# bulb-2.net
KiCad netlist of a schematic drawn in EAGLE
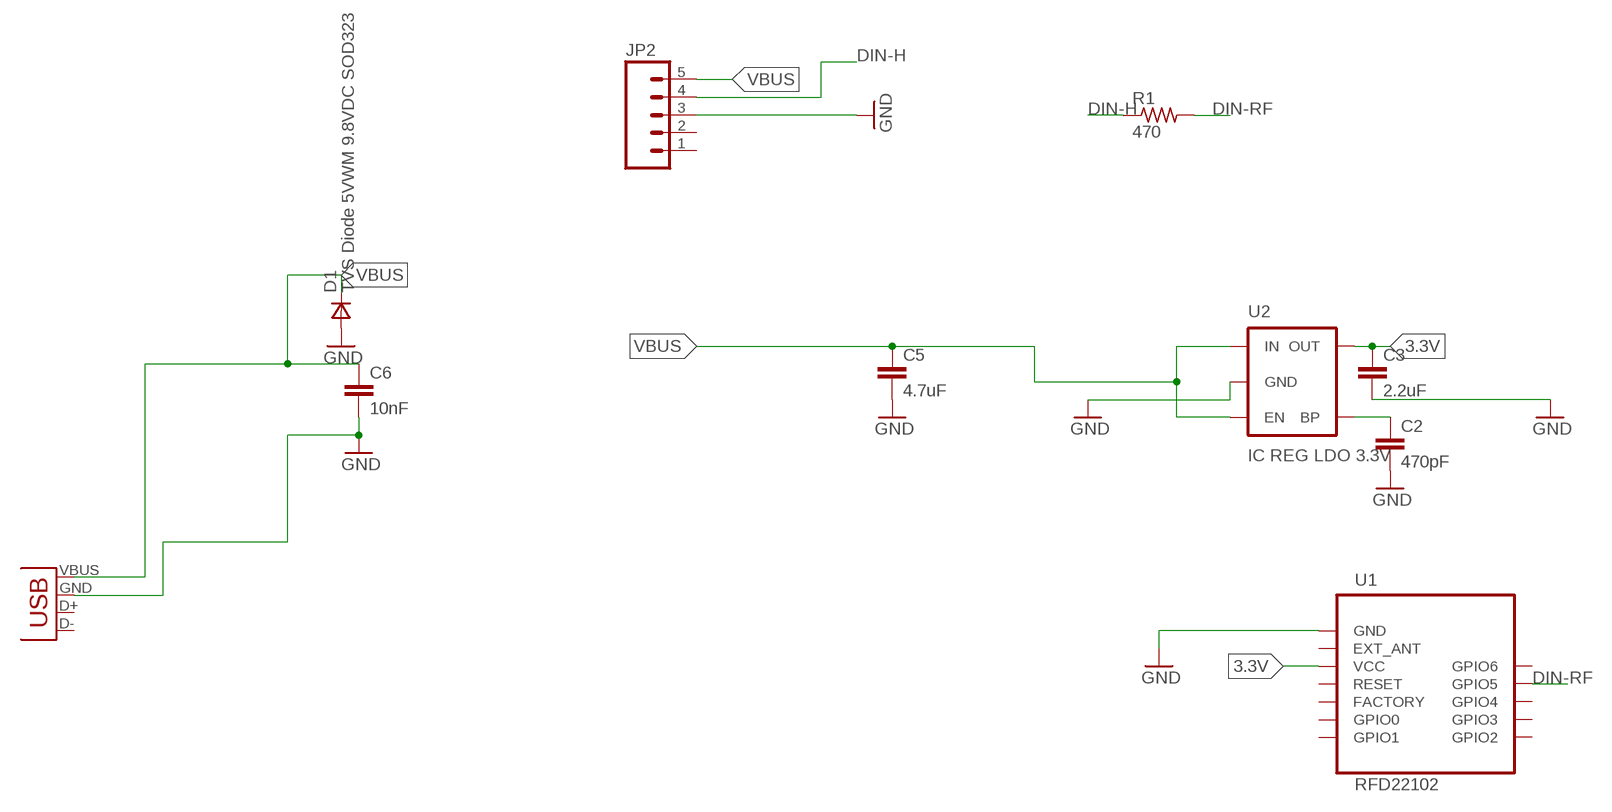
[diagram p0: schematic, sheet 1]

(export (version "E")
  (design (tool "Eeschema 10.0.6"))
  (components
    (comp (ref "C2")
      (value "470pF")
      (footprint "eagle-import:0603-CAP")
      (libsource (lib "eagle-import") (part "470PF-50V-5%(0603)SMD"))
    )
    (comp (ref "C3")
      (value "2.2uF")
      (footprint "eagle-import:0603-CAP")
      (libsource (lib "eagle-import") (part "2.2UF-10V-20%(0603)"))
    )
    (comp (ref "C5")
      (value "4.7uF")
      (footprint "eagle-import:0603-CAP")
      (libsource (lib "eagle-import") (part "4.7UF-6.3V-10%(0603)0603"))
    )
    (comp (ref "C6")
      (value "10nF")
      (footprint "eagle-import:0603-CAP")
      (libsource (lib "eagle-import") (part "10NF/10000PF-50V-10%(0603)"))
    )
    (comp (ref "D1")
      (value "TVS Diode 5VWM 9.8VDC SOD323")
      (footprint "eagle-import:SOD323")
      (fields (field (name "MPN") "CDSOD323-T05C"))
      (libsource (lib "eagle-import") (part "DSOD323"))
    )
    (comp (ref "JP1")
      (value "USB-A-H")
      (footprint "eagle-import:USB-A-H")
      (libsource (lib "eagle-import") (part "USB-A-H"))
    )
    (comp (ref "JP2")
      (value "M05PTH")
      (footprint "eagle-import:1X05")
      (libsource (lib "eagle-import") (part "M05PTH"))
    )
    (comp (ref "R1")
      (value "470")
      (footprint "eagle-import:R0603")
      (libsource (lib "eagle-import") (part "R-US_R0603"))
    )
    (comp (ref "U1")
      (value "RFD22102")
      (footprint "eagle-import:RFD22102")
      (libsource (lib "eagle-import") (part "RFD22102"))
    )
    (comp (ref "U2")
      (value "IC REG LDO 3.3V")
      (footprint "eagle-import:SOT23-5")
      (libsource (lib "eagle-import") (part "MIC52053.3V"))
    )
  )
  (nets
    (net (code "1") (name "/DIN-H") (class "Default")
      (node (ref "JP2") (pin "4") (pinfunction "4_4") (pintype "passive"))
      (node (ref "R1") (pin "1") (pinfunction "1_1") (pintype "passive"))
    )
    (net (code "2") (name "/DIN-RF") (class "Default")
      (node (ref "R1") (pin "2") (pinfunction "2_2") (pintype "passive"))
      (node (ref "U1") (pin "GPIO5") (pinfunction "GPIO5_GPIO5") (pintype "bidirectional"))
    )
    (net (code "3") (name "3.3V") (class "Default")
      (node (ref "C3") (pin "1") (pinfunction "1_1") (pintype "passive"))
      (node (ref "U1") (pin "VCC") (pinfunction "VCC_VCC") (pintype "power_in"))
      (node (ref "U2") (pin "5") (pinfunction "OUT_5") (pintype "passive"))
    )
    (net (code "4") (name "GND") (class "Default")
      (node (ref "C2") (pin "2") (pinfunction "2_2") (pintype "passive"))
      (node (ref "C3") (pin "2") (pinfunction "2_2") (pintype "passive"))
      (node (ref "C5") (pin "2") (pinfunction "2_2") (pintype "passive"))
      (node (ref "C6") (pin "2") (pinfunction "2_2") (pintype "passive"))
      (node (ref "D1") (pin "2") (pinfunction "A_2") (pintype "passive"))
      (node (ref "JP1") (pin "GND") (pinfunction "VBUS_GND") (pintype "bidirectional"))
      (node (ref "JP2") (pin "3") (pinfunction "3_3") (pintype "passive"))
      (node (ref "U1") (pin "GND") (pinfunction "GND_GND") (pintype "power_in"))
      (node (ref "U2") (pin "2") (pinfunction "GND_2") (pintype "input"))
    )
    (net (code "5") (name "Net-(U2-BP)") (class "Default")
      (node (ref "C2") (pin "1") (pinfunction "1_1") (pintype "passive"))
      (node (ref "U2") (pin "4") (pinfunction "BP_4") (pintype "input"))
    )
    (net (code "6") (name "VBUS") (class "Default")
      (node (ref "C5") (pin "1") (pinfunction "1_1") (pintype "passive"))
      (node (ref "C6") (pin "1") (pinfunction "1_1") (pintype "passive"))
      (node (ref "D1") (pin "1") (pinfunction "C_1") (pintype "passive"))
      (node (ref "JP1") (pin "VBUS") (pinfunction "GND_VBUS") (pintype "bidirectional"))
      (node (ref "JP2") (pin "5") (pinfunction "5_5") (pintype "passive"))
      (node (ref "U2") (pin "1") (pinfunction "IN_1") (pintype "input"))
      (node (ref "U2") (pin "3") (pinfunction "EN_3") (pintype "input"))
    )
    (net (code "7") (name "unconnected-(JP1-D+-PadD-)") (class "Default")
      (node (ref "JP1") (pin "D-") (pinfunction "D+_D-") (pintype "bidirectional"))
    )
    (net (code "8") (name "unconnected-(JP1-D--PadD+)") (class "Default")
      (node (ref "JP1") (pin "D+") (pinfunction "D-_D+") (pintype "bidirectional"))
    )
    (net (code "9") (name "unconnected-(JP2-Pad1)") (class "Default")
      (node (ref "JP2") (pin "1") (pinfunction "1_1") (pintype "passive"))
    )
    (net (code "10") (name "unconnected-(JP2-Pad2)") (class "Default")
      (node (ref "JP2") (pin "2") (pinfunction "2_2") (pintype "passive"))
    )
    (net (code "11") (name "unconnected-(U1-PadEXT_ANT)") (class "Default")
      (node (ref "U1") (pin "EXT_ANT") (pinfunction "EXT_ANT_EXT_ANT") (pintype "no_connect"))
    )
    (net (code "12") (name "unconnected-(U1-PadFACTORY)") (class "Default")
      (node (ref "U1") (pin "FACTORY") (pinfunction "FACTORY_FACTORY") (pintype "bidirectional"))
    )
    (net (code "13") (name "unconnected-(U1-PadGPIO0)") (class "Default")
      (node (ref "U1") (pin "GPIO0") (pinfunction "GPIO0_GPIO0") (pintype "bidirectional"))
    )
    (net (code "14") (name "unconnected-(U1-PadGPIO1)") (class "Default")
      (node (ref "U1") (pin "GPIO1") (pinfunction "GPIO1_GPIO1") (pintype "bidirectional"))
    )
    (net (code "15") (name "unconnected-(U1-PadGPIO2)") (class "Default")
      (node (ref "U1") (pin "GPIO2") (pinfunction "GPIO2_GPIO2") (pintype "bidirectional"))
    )
    (net (code "16") (name "unconnected-(U1-PadGPIO3)") (class "Default")
      (node (ref "U1") (pin "GPIO3") (pinfunction "GPIO3_GPIO3") (pintype "bidirectional"))
    )
    (net (code "17") (name "unconnected-(U1-PadGPIO4)") (class "Default")
      (node (ref "U1") (pin "GPIO4") (pinfunction "GPIO4_GPIO4") (pintype "bidirectional"))
    )
    (net (code "18") (name "unconnected-(U1-PadGPIO6)") (class "Default")
      (node (ref "U1") (pin "GPIO6") (pinfunction "GPIO6_GPIO6") (pintype "bidirectional"))
    )
    (net (code "19") (name "unconnected-(U1-PadRESET)") (class "Default")
      (node (ref "U1") (pin "RESET") (pinfunction "RESET_RESET") (pintype "bidirectional"))
    )
  )
)
